# TSOC_RS485_EM.net
KiCad netlist of a schematic drawn in EAGLE
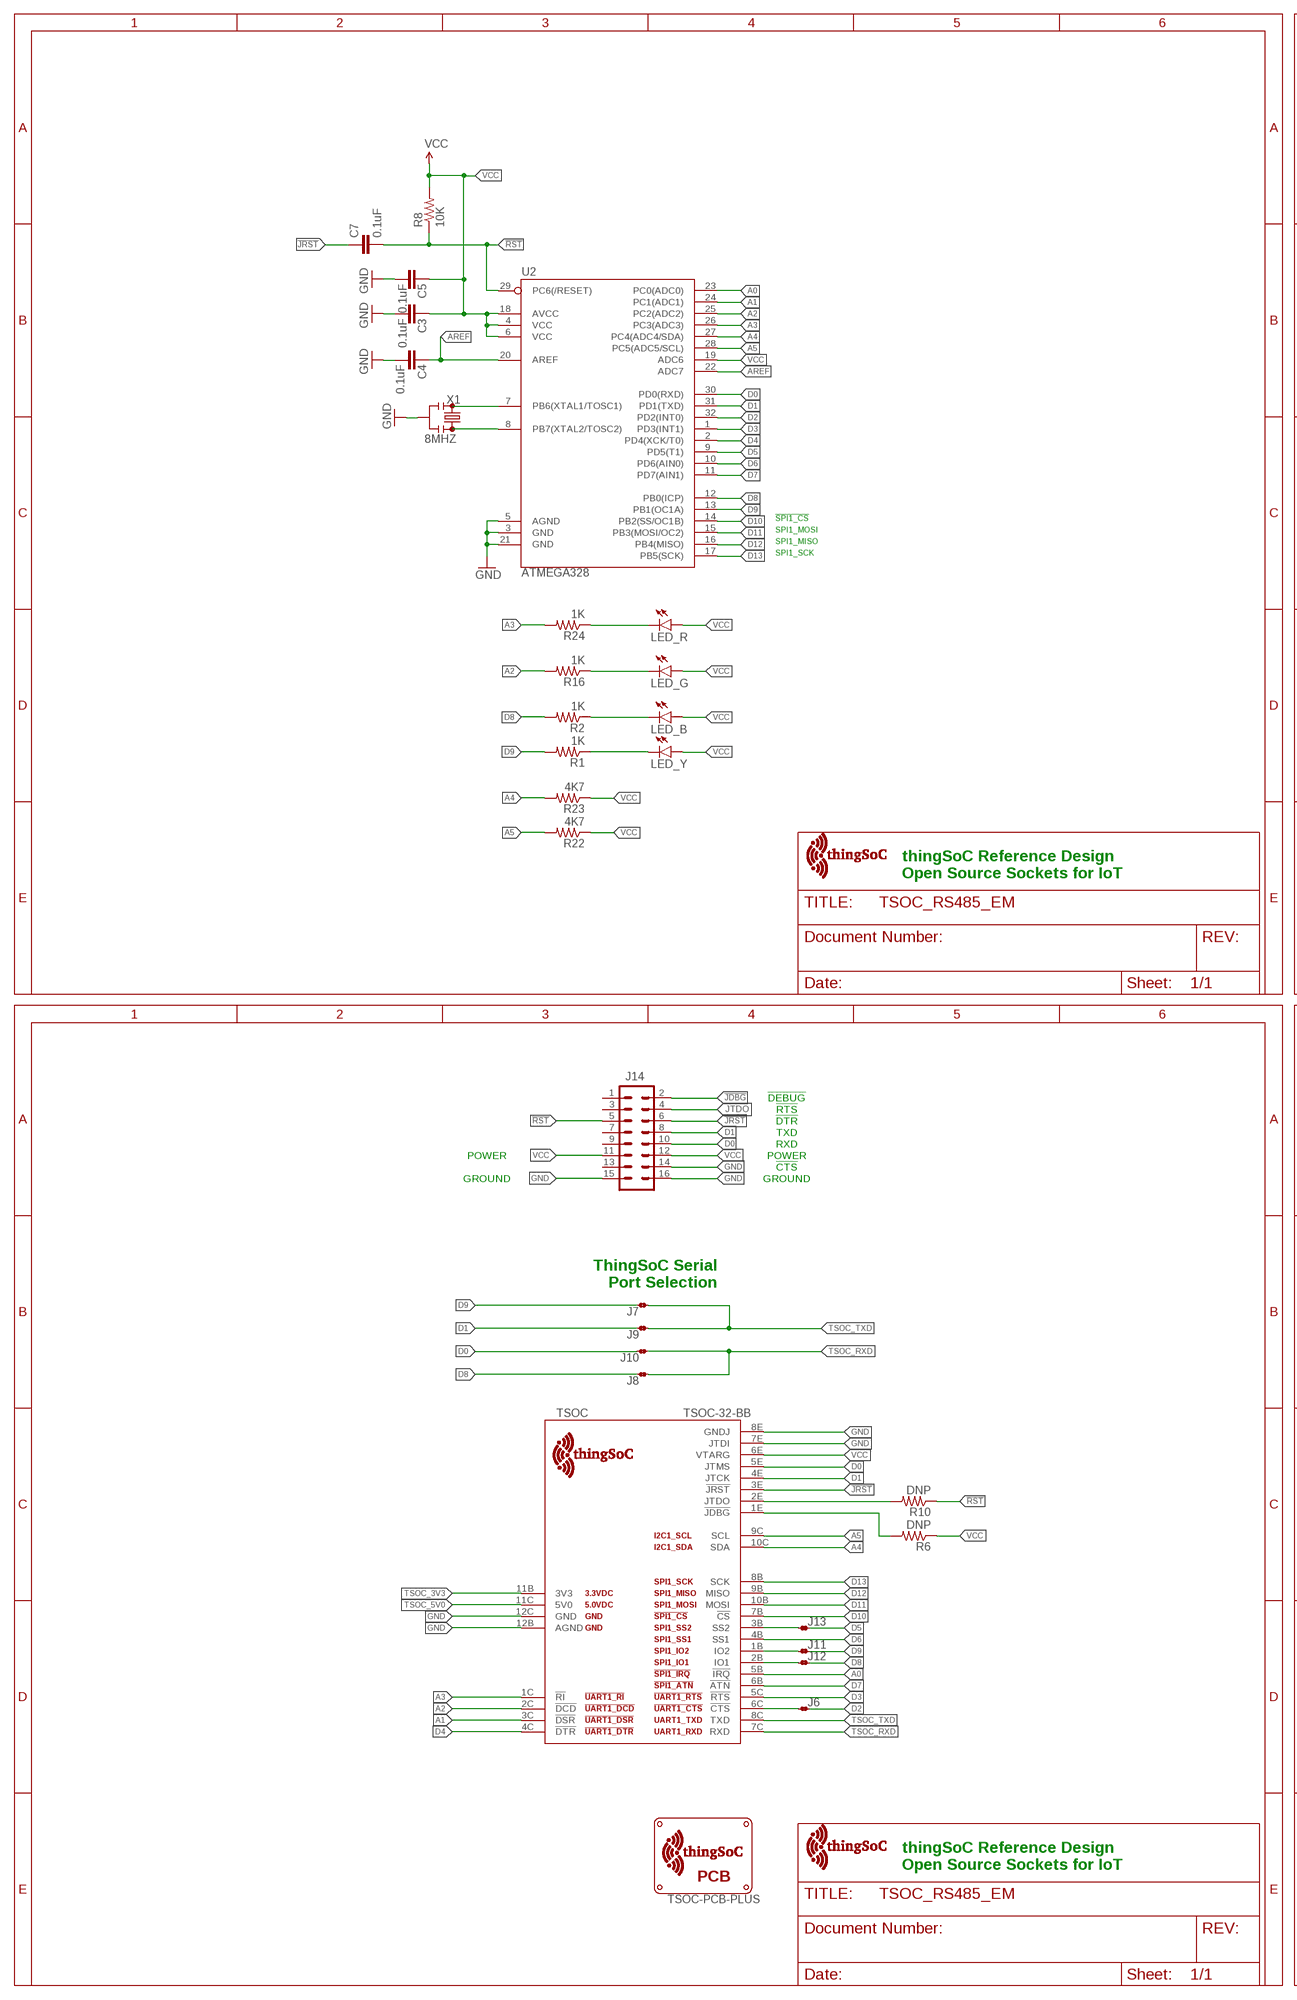
[diagram p0: schematic, sheet 1, part 1 of 2]
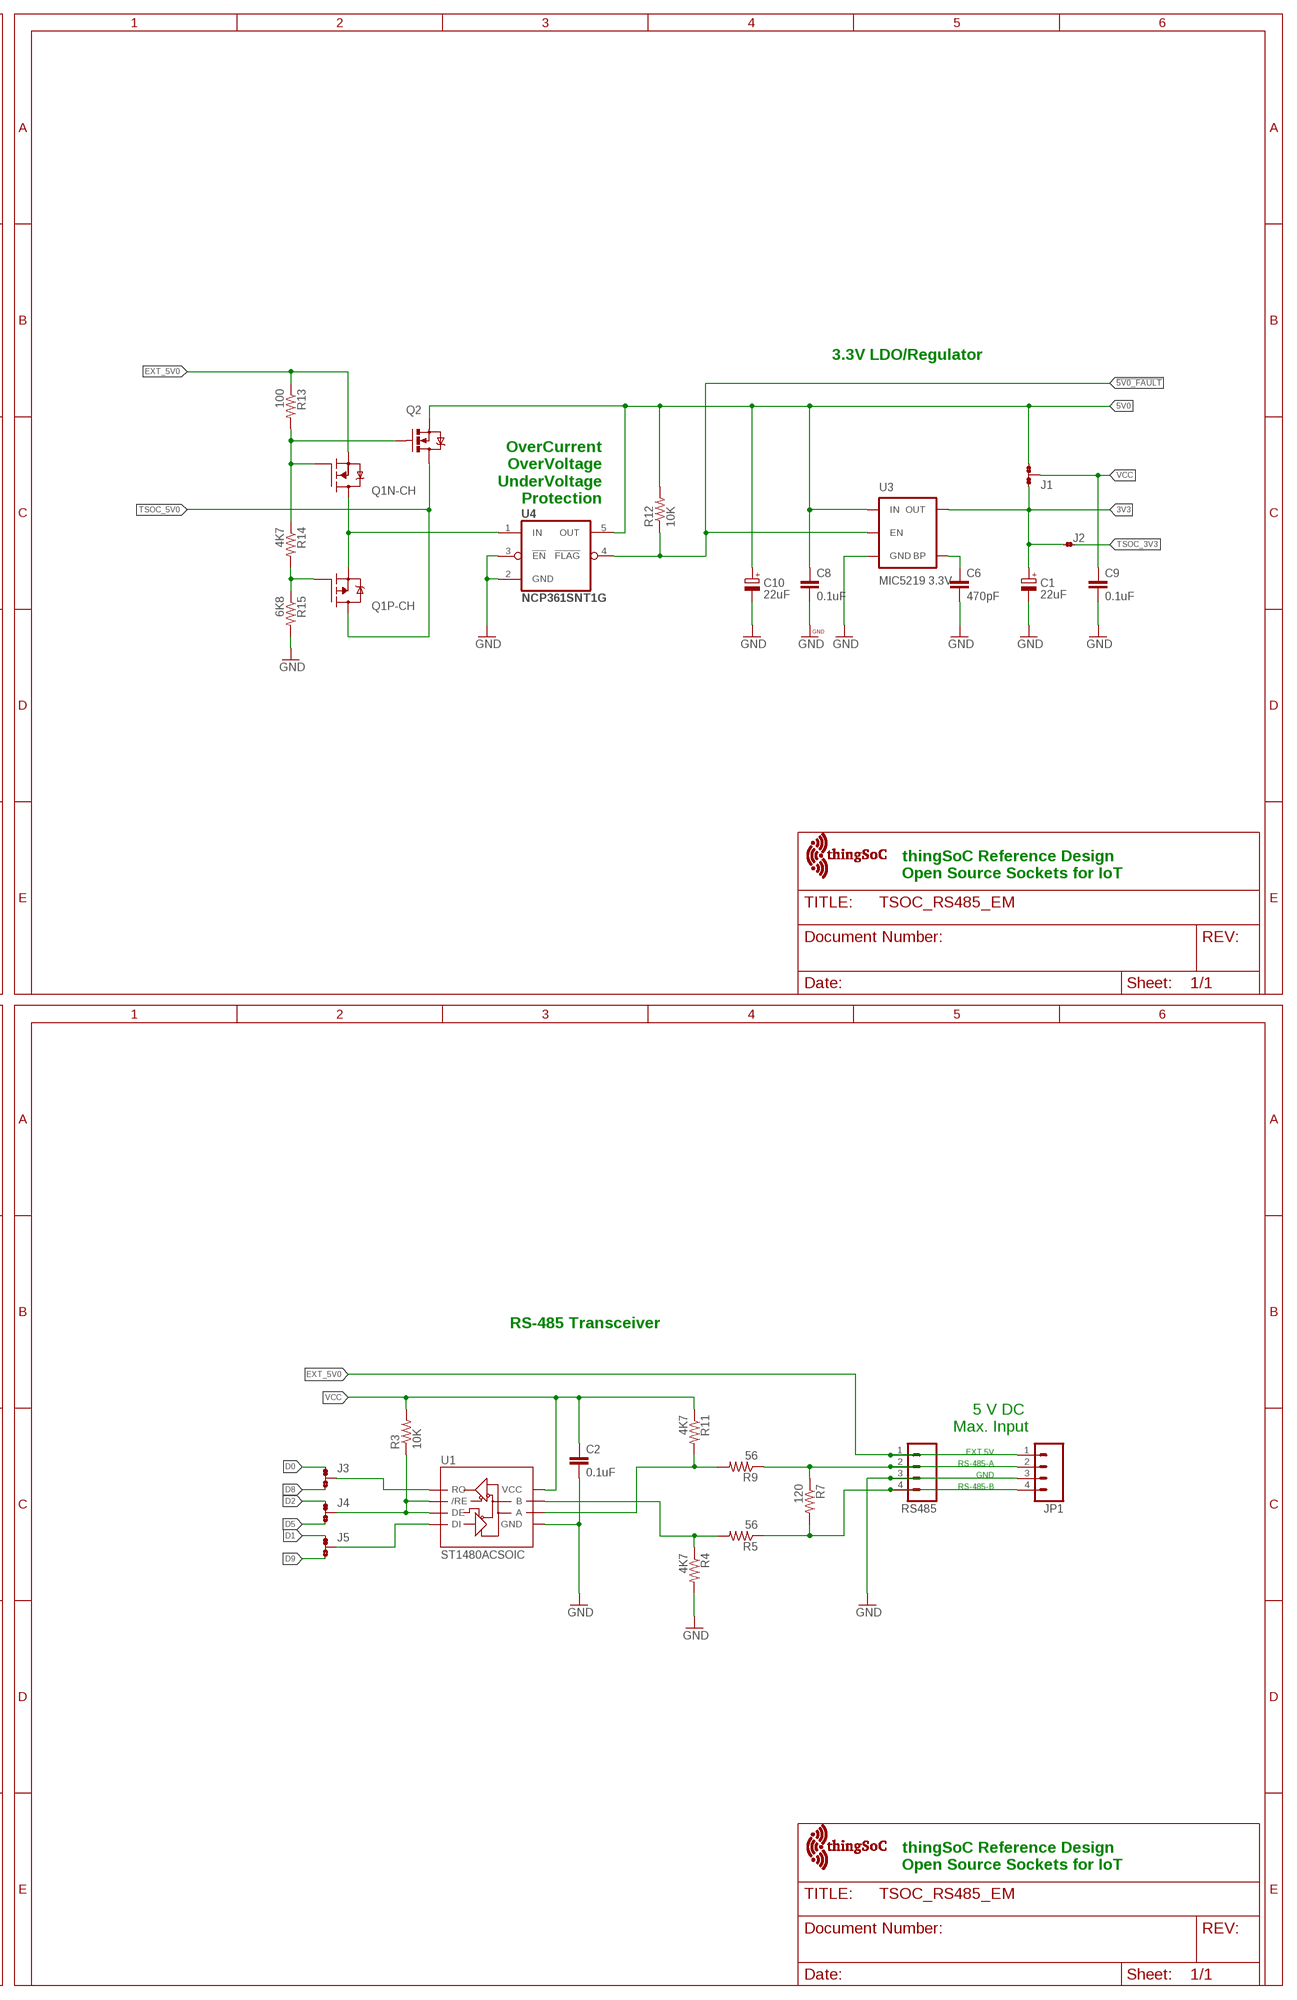
[diagram p1: schematic, sheet 1, part 2 of 2]

(export (version "E")
  (design (tool "Eeschema 10.0.6"))
  (components
    (comp (ref "C1")
      (value "22uF")
      (footprint "eagle-import:SMC_B")
      (libsource (lib "eagle-import") (part "CPOL-EUSMCB"))
    )
    (comp (ref "C2")
      (value "0.1uF")
      (footprint "eagle-import:EIA-0402")
      (libsource (lib "eagle-import") (part "CAPTYP"))
    )
    (comp (ref "C3")
      (value "0.1uF")
      (footprint "eagle-import:EIA-0402")
      (libsource (lib "eagle-import") (part "CAPTYP"))
    )
    (comp (ref "C4")
      (value "0.1uF")
      (footprint "eagle-import:EIA-0402")
      (libsource (lib "eagle-import") (part "CAPTYP"))
    )
    (comp (ref "C5")
      (value "0.1uF")
      (footprint "eagle-import:EIA-0402")
      (libsource (lib "eagle-import") (part "CAPTYP"))
    )
    (comp (ref "C6")
      (value "470pF")
      (footprint "eagle-import:EIA-0402")
      (libsource (lib "eagle-import") (part "CAPTYP"))
    )
    (comp (ref "C7")
      (value "0.1uF")
      (footprint "eagle-import:EIA-0402")
      (libsource (lib "eagle-import") (part "CAPTYP"))
    )
    (comp (ref "C8")
      (value "0.1uF")
      (footprint "eagle-import:EIA-0402")
      (libsource (lib "eagle-import") (part "CAPTYP"))
    )
    (comp (ref "C9")
      (value "0.1uF")
      (footprint "eagle-import:EIA-0402")
      (libsource (lib "eagle-import") (part "CAPTYP"))
    )
    (comp (ref "C10")
      (value "22uF")
      (footprint "eagle-import:SMC_B")
      (libsource (lib "eagle-import") (part "CPOL-EUSMCB"))
    )
    (comp (ref "J1")
      (value "JMP-3-1_2")
      (footprint "eagle-import:JMP-3-1_2")
      (libsource (lib "eagle-import") (part "JMP-3-1_2"))
    )
    (comp (ref "J2")
      (value "JMP-2-NC")
      (footprint "eagle-import:JMP-2-NC")
      (libsource (lib "eagle-import") (part "JMP-2-NC"))
    )
    (comp (ref "J3")
      (value "JMP-3-1_2")
      (footprint "eagle-import:JMP-3-1_2")
      (libsource (lib "eagle-import") (part "TSOC_RS485_EM_JMP-3-1_2"))
    )
    (comp (ref "J4")
      (value "JMP-3-1_2")
      (footprint "eagle-import:JMP-3-1_2")
      (libsource (lib "eagle-import") (part "TSOC_RS485_EM_JMP-3-1_2"))
    )
    (comp (ref "J5")
      (value "JMP-3-1_2")
      (footprint "eagle-import:JMP-3-1_2")
      (libsource (lib "eagle-import") (part "TSOC_RS485_EM_JMP-3-1_2"))
    )
    (comp (ref "J6")
      (value "JMP-2-NO")
      (footprint "eagle-import:JMP-2-NO")
      (libsource (lib "eagle-import") (part "JMP-2-NO"))
    )
    (comp (ref "J7")
      (value "JMP-2-NO")
      (footprint "eagle-import:JMP-2-NO")
      (libsource (lib "eagle-import") (part "JMP-2-NO"))
    )
    (comp (ref "J8")
      (value "JMP-2-NO")
      (footprint "eagle-import:JMP-2-NO")
      (libsource (lib "eagle-import") (part "JMP-2-NO"))
    )
    (comp (ref "J9")
      (value "JMP-2-NO")
      (footprint "eagle-import:JMP-2-NO")
      (libsource (lib "eagle-import") (part "JMP-2-NO"))
    )
    (comp (ref "J10")
      (value "JMP-2-NO")
      (footprint "eagle-import:JMP-2-NO")
      (libsource (lib "eagle-import") (part "JMP-2-NO"))
    )
    (comp (ref "J11")
      (value "JMP-2-NC")
      (footprint "eagle-import:JMP-2-NC")
      (libsource (lib "eagle-import") (part "JMP-2-NC"))
    )
    (comp (ref "J12")
      (value "JMP-2-NC")
      (footprint "eagle-import:JMP-2-NC")
      (libsource (lib "eagle-import") (part "JMP-2-NC"))
    )
    (comp (ref "J13")
      (value "JMP-2-NC")
      (footprint "eagle-import:JMP-2-NC")
      (libsource (lib "eagle-import") (part "JMP-2-NC"))
    )
    (comp (ref "J14")
      (value "M08X2")
      (footprint "eagle-import:2X8")
      (libsource (lib "eagle-import") (part "M08X2"))
    )
    (comp (ref "JP1")
      (value "M04PTH")
      (footprint "eagle-import:1X04")
      (libsource (lib "eagle-import") (part "M04PTH"))
    )
    (comp (ref "LED_B")
      (value "LED0603")
      (footprint "eagle-import:LED-0603")
      (libsource (lib "eagle-import") (part "LED0603"))
    )
    (comp (ref "LED_G")
      (value "LED0603")
      (footprint "eagle-import:LED-0603")
      (libsource (lib "eagle-import") (part "LED0603"))
    )
    (comp (ref "LED_R")
      (value "LED0603")
      (footprint "eagle-import:LED-0603")
      (libsource (lib "eagle-import") (part "LED0603"))
    )
    (comp (ref "LED_Y")
      (value "LED0603")
      (footprint "eagle-import:LED-0603")
      (libsource (lib "eagle-import") (part "LED0603"))
    )
    (comp (ref "Q1")
      (value "FDC6420C")
      (footprint "eagle-import:SOT95P280X110-6N")
      (libsource (lib "eagle-import") (part "FDC6420C"))
    )
    (comp (ref "Q2")
      (value "MOSFET-NCHANNELAO3404A")
      (footprint "eagle-import:SOT23-3")
      (libsource (lib "eagle-import") (part "MOSFET-NCHANNELAO3404A"))
    )
    (comp (ref "R1")
      (value "1K")
      (footprint "eagle-import:EIA-0402-MIN")
      (libsource (lib "eagle-import") (part "RESISTOR0402-MIN"))
    )
    (comp (ref "R2")
      (value "1K")
      (footprint "eagle-import:EIA-0402-MIN")
      (libsource (lib "eagle-import") (part "RESISTOR0402-MIN"))
    )
    (comp (ref "R3")
      (value "10K")
      (footprint "eagle-import:EIA-0402-MIN")
      (libsource (lib "eagle-import") (part "RESISTOR0402-MIN"))
    )
    (comp (ref "R4")
      (value "4K7")
      (footprint "eagle-import:EIA-0402-MIN")
      (libsource (lib "eagle-import") (part "RESISTOR0402-MIN"))
    )
    (comp (ref "R5")
      (value "56")
      (footprint "eagle-import:EIA-0402-MIN")
      (libsource (lib "eagle-import") (part "RESISTOR0402-MIN"))
    )
    (comp (ref "R6")
      (value "DNP")
      (footprint "eagle-import:EIA-0402-MIN")
      (libsource (lib "eagle-import") (part "RESISTOR0402-MIN"))
    )
    (comp (ref "R7")
      (value "120")
      (footprint "eagle-import:EIA-0402-MIN")
      (libsource (lib "eagle-import") (part "RESISTOR0402-MIN"))
    )
    (comp (ref "R8")
      (value "10K")
      (footprint "eagle-import:EIA-0402-MIN")
      (libsource (lib "eagle-import") (part "RESISTOR0402-MIN"))
    )
    (comp (ref "R9")
      (value "56")
      (footprint "eagle-import:EIA-0402-MIN")
      (libsource (lib "eagle-import") (part "RESISTOR0402-MIN"))
    )
    (comp (ref "R10")
      (value "DNP")
      (footprint "eagle-import:EIA-0402-MIN")
      (libsource (lib "eagle-import") (part "RESISTOR0402-MIN"))
    )
    (comp (ref "R11")
      (value "4K7")
      (footprint "eagle-import:EIA-0402-MIN")
      (libsource (lib "eagle-import") (part "RESISTOR0402-MIN"))
    )
    (comp (ref "R12")
      (value "10K")
      (footprint "eagle-import:EIA-0402-MIN")
      (libsource (lib "eagle-import") (part "RESISTOR0402-MIN"))
    )
    (comp (ref "R13")
      (value "100")
      (footprint "eagle-import:EIA-0402-MIN")
      (libsource (lib "eagle-import") (part "RESISTOR0402-MIN"))
    )
    (comp (ref "R14")
      (value "4K7")
      (footprint "eagle-import:EIA-0402-MIN")
      (libsource (lib "eagle-import") (part "RESISTOR0402-MIN"))
    )
    (comp (ref "R15")
      (value "6K8")
      (footprint "eagle-import:EIA-0402-MIN")
      (libsource (lib "eagle-import") (part "RESISTOR0402-MIN"))
    )
    (comp (ref "R16")
      (value "1K")
      (footprint "eagle-import:EIA-0402-MIN")
      (libsource (lib "eagle-import") (part "RESISTOR0402-MIN"))
    )
    (comp (ref "R22")
      (value "4K7")
      (footprint "eagle-import:EIA-0402-MIN")
      (libsource (lib "eagle-import") (part "RESISTOR0402-MIN"))
    )
    (comp (ref "R23")
      (value "4K7")
      (footprint "eagle-import:EIA-0402-MIN")
      (libsource (lib "eagle-import") (part "RESISTOR0402-MIN"))
    )
    (comp (ref "R24")
      (value "1K")
      (footprint "eagle-import:EIA-0402-MIN")
      (libsource (lib "eagle-import") (part "RESISTOR0402-MIN"))
    )
    (comp (ref "RS485")
      (value "M04SCREW")
      (footprint "eagle-import:SCREWTERMINAL-3.5MM-4")
      (libsource (lib "eagle-import") (part "M04SCREW"))
    )
    (comp (ref "TSOC")
      (value "TSOC-32-BB")
      (footprint "eagle-import:TSOC-BB-S32")
      (libsource (lib "eagle-import") (part "TSOC-32-BB"))
    )
    (comp (ref "U$3")
      (value "TSOC-PCB-PLUS")
      (footprint "eagle-import:TSOC-BB-BRD-PLUS")
      (libsource (lib "eagle-import") (part "TSOC-PCB-PLUS"))
    )
    (comp (ref "U$5")
      (value "TSOC-LOGO-SMALL")
      (footprint "eagle-import:TSOC-LOGO-SML")
      (libsource (lib "eagle-import") (part "TSOC-LOGO-SMALL"))
    )
    (comp (ref "U$6")
      (value "TSOC-LOGO-SMALL")
      (footprint "eagle-import:TSOC-LOGO-SML")
      (libsource (lib "eagle-import") (part "TSOC-LOGO-SMALL"))
    )
    (comp (ref "U$7")
      (value "TSOC-LOGO-SMALL")
      (footprint "eagle-import:TSOC-LOGO-SML")
      (libsource (lib "eagle-import") (part "TSOC-LOGO-SMALL"))
    )
    (comp (ref "U$8")
      (value "TSOC-LOGO-SMALL")
      (footprint "eagle-import:TSOC-LOGO-SML")
      (libsource (lib "eagle-import") (part "TSOC-LOGO-SMALL"))
    )
    (comp (ref "U1")
      (value "ST1480ACSOIC")
      (footprint "eagle-import:SO08")
      (libsource (lib "eagle-import") (part "ST1480ACSOIC"))
    )
    (comp (ref "U2")
      (value "ATMEGA328")
      (footprint "eagle-import:TQFP32-08")
      (libsource (lib "eagle-import") (part "ATMEGA168"))
    )
    (comp (ref "U3")
      (value "MIC5219 3.3V")
      (footprint "eagle-import:SOT23-5")
      (libsource (lib "eagle-import") (part "V_REG_MIC52193.3V"))
    )
    (comp (ref "U4")
      (value "NCP361SNT1G")
      (footprint "eagle-import:SOP95P275X110-5N")
      (libsource (lib "eagle-import") (part "NCP361SNT1G"))
    )
    (comp (ref "X1")
      (value "8MHZ")
      (footprint "eagle-import:RESONATOR-SMD")
      (libsource (lib "eagle-import") (part "RESONATOR8MHZ"))
    )
  )
  (nets
    (net (code "1") (name "/~{5V0_FAULT}") (class "Default")
      (node (ref "R12") (pin "1") (pinfunction "1_1") (pintype "passive"))
      (node (ref "U3") (pin "3") (pinfunction "EN_3") (pintype "input"))
      (node (ref "U4") (pin "4") (pinfunction "~{FLAG}_4") (pintype "input"))
    )
    (net (code "2") (name "/~{JDBG}") (class "Default")
      (node (ref "J14") (pin "2") (pinfunction "2_2") (pintype "passive"))
      (node (ref "R6") (pin "2") (pinfunction "2_2") (pintype "passive"))
      (node (ref "TSOC") (pin "1E") (pinfunction "~{JDBG}_1E") (pintype "bidirectional"))
    )
    (net (code "3") (name "/~{JRST}") (class "Default")
      (node (ref "C7") (pin "1") (pinfunction "1_1") (pintype "passive"))
      (node (ref "J14") (pin "6") (pinfunction "6_6") (pintype "passive"))
      (node (ref "TSOC") (pin "3E") (pinfunction "~{JRST}_3E") (pintype "bidirectional"))
    )
    (net (code "4") (name "/~{RST}") (class "Default")
      (node (ref "C7") (pin "2") (pinfunction "2_2") (pintype "passive"))
      (node (ref "J14") (pin "5") (pinfunction "5_5") (pintype "passive"))
      (node (ref "R10") (pin "1") (pinfunction "1_1") (pintype "passive"))
      (node (ref "R8") (pin "1") (pinfunction "1_1") (pintype "passive"))
      (node (ref "U2") (pin "29") (pinfunction "PC6(/RESET)_29") (pintype "bidirectional"))
    )
    (net (code "5") (name "3V3") (class "Default")
      (node (ref "C1") (pin "+") (pinfunction "+_+") (pintype "passive"))
      (node (ref "J1") (pin "1") (pinfunction "1_1") (pintype "passive"))
      (node (ref "J2") (pin "1") (pinfunction "1_1") (pintype "passive"))
      (node (ref "U3") (pin "5") (pinfunction "OUT_5") (pintype "passive"))
    )
    (net (code "6") (name "5V0") (class "Default")
      (node (ref "C10") (pin "+") (pinfunction "+_+") (pintype "passive"))
      (node (ref "C8") (pin "1") (pinfunction "1_1") (pintype "passive"))
      (node (ref "J1") (pin "3") (pinfunction "3_3") (pintype "passive"))
      (node (ref "Q2") (pin "2") (pinfunction "S_2") (pintype "passive"))
      (node (ref "R12") (pin "2") (pinfunction "2_2") (pintype "passive"))
      (node (ref "U3") (pin "1") (pinfunction "IN_1") (pintype "input"))
      (node (ref "U4") (pin "5") (pinfunction "OUT_5") (pintype "output"))
    )
    (net (code "7") (name "A0") (class "Default")
      (node (ref "TSOC") (pin "5B") (pinfunction "~{IRQ}_5B") (pintype "bidirectional"))
      (node (ref "U2") (pin "23") (pinfunction "PC0(ADC0)_23") (pintype "bidirectional"))
    )
    (net (code "8") (name "A1") (class "Default")
      (node (ref "TSOC") (pin "3C") (pinfunction "~{DSR}_3C") (pintype "bidirectional"))
      (node (ref "U2") (pin "24") (pinfunction "PC1(ADC1)_24") (pintype "bidirectional"))
    )
    (net (code "9") (name "A2") (class "Default")
      (node (ref "R16") (pin "2") (pinfunction "2_2") (pintype "passive"))
      (node (ref "TSOC") (pin "2C") (pinfunction "~{DCD}_2C") (pintype "bidirectional"))
      (node (ref "U2") (pin "25") (pinfunction "PC2(ADC2)_25") (pintype "bidirectional"))
    )
    (net (code "10") (name "A3") (class "Default")
      (node (ref "R24") (pin "2") (pinfunction "2_2") (pintype "passive"))
      (node (ref "TSOC") (pin "1C") (pinfunction "~{RI}_1C") (pintype "bidirectional"))
      (node (ref "U2") (pin "26") (pinfunction "PC3(ADC3)_26") (pintype "bidirectional"))
    )
    (net (code "11") (name "A4") (class "Default")
      (node (ref "R23") (pin "2") (pinfunction "2_2") (pintype "passive"))
      (node (ref "TSOC") (pin "10C") (pinfunction "SDA_10C") (pintype "bidirectional"))
      (node (ref "U2") (pin "27") (pinfunction "PC4(ADC4/SDA)_27") (pintype "bidirectional"))
    )
    (net (code "12") (name "A5") (class "Default")
      (node (ref "R22") (pin "2") (pinfunction "2_2") (pintype "passive"))
      (node (ref "TSOC") (pin "9C") (pinfunction "SCL_9C") (pintype "bidirectional"))
      (node (ref "U2") (pin "28") (pinfunction "PC5(ADC5/SCL)_28") (pintype "bidirectional"))
    )
    (net (code "13") (name "AREF") (class "Default")
      (node (ref "C4") (pin "2") (pinfunction "2_2") (pintype "passive"))
      (node (ref "U2") (pin "20") (pinfunction "AREF_20") (pintype "bidirectional"))
      (node (ref "U2") (pin "22") (pinfunction "ADC7_22") (pintype "bidirectional"))
    )
    (net (code "14") (name "D0") (class "Default")
      (node (ref "J10") (pin "2") (pinfunction "2_2") (pintype "passive"))
      (node (ref "J14") (pin "10") (pinfunction "10_10") (pintype "passive"))
      (node (ref "J3") (pin "1") (pinfunction "1_1") (pintype "passive"))
      (node (ref "TSOC") (pin "5E") (pinfunction "JTMS_5E") (pintype "bidirectional"))
      (node (ref "U2") (pin "30") (pinfunction "PD0(RXD)_30") (pintype "bidirectional"))
    )
    (net (code "15") (name "D1") (class "Default")
      (node (ref "J14") (pin "8") (pinfunction "8_8") (pintype "passive"))
      (node (ref "J5") (pin "1") (pinfunction "1_1") (pintype "passive"))
      (node (ref "J9") (pin "2") (pinfunction "2_2") (pintype "passive"))
      (node (ref "TSOC") (pin "4E") (pinfunction "JTCK_4E") (pintype "bidirectional"))
      (node (ref "U2") (pin "31") (pinfunction "PD1(TXD)_31") (pintype "bidirectional"))
    )
    (net (code "16") (name "D2") (class "Default")
      (node (ref "J4") (pin "1") (pinfunction "1_1") (pintype "passive"))
      (node (ref "J6") (pin "2") (pinfunction "2_2") (pintype "passive"))
      (node (ref "U2") (pin "32") (pinfunction "PD2(INT0)_32") (pintype "bidirectional"))
    )
    (net (code "17") (name "D3") (class "Default")
      (node (ref "TSOC") (pin "5C") (pinfunction "~{RTS}_5C") (pintype "bidirectional"))
      (node (ref "U2") (pin "1") (pinfunction "PD3(INT1)_1") (pintype "bidirectional"))
    )
    (net (code "18") (name "D4") (class "Default")
      (node (ref "TSOC") (pin "4C") (pinfunction "~{DTR}_4C") (pintype "bidirectional"))
      (node (ref "U2") (pin "2") (pinfunction "PD4(XCK/T0)_2") (pintype "bidirectional"))
    )
    (net (code "19") (name "D5") (class "Default")
      (node (ref "J13") (pin "2") (pinfunction "2_2") (pintype "passive"))
      (node (ref "J4") (pin "3") (pinfunction "3_3") (pintype "passive"))
      (node (ref "U2") (pin "9") (pinfunction "PD5(T1)_9") (pintype "bidirectional"))
    )
    (net (code "20") (name "D6") (class "Default")
      (node (ref "TSOC") (pin "4B") (pinfunction "SS1_4B") (pintype "bidirectional"))
      (node (ref "U2") (pin "10") (pinfunction "PD6(AIN0)_10") (pintype "bidirectional"))
    )
    (net (code "21") (name "D7") (class "Default")
      (node (ref "TSOC") (pin "6B") (pinfunction "~{ATN}_6B") (pintype "bidirectional"))
      (node (ref "U2") (pin "11") (pinfunction "PD7(AIN1)_11") (pintype "bidirectional"))
    )
    (net (code "22") (name "D8") (class "Default")
      (node (ref "J12") (pin "2") (pinfunction "2_2") (pintype "passive"))
      (node (ref "J3") (pin "3") (pinfunction "3_3") (pintype "passive"))
      (node (ref "J8") (pin "2") (pinfunction "2_2") (pintype "passive"))
      (node (ref "R2") (pin "2") (pinfunction "2_2") (pintype "passive"))
      (node (ref "U2") (pin "12") (pinfunction "PB0(ICP)_12") (pintype "bidirectional"))
    )
    (net (code "23") (name "D9") (class "Default")
      (node (ref "J11") (pin "2") (pinfunction "2_2") (pintype "passive"))
      (node (ref "J5") (pin "3") (pinfunction "3_3") (pintype "passive"))
      (node (ref "J7") (pin "2") (pinfunction "2_2") (pintype "passive"))
      (node (ref "R1") (pin "2") (pinfunction "2_2") (pintype "passive"))
      (node (ref "U2") (pin "13") (pinfunction "PB1(OC1A)_13") (pintype "bidirectional"))
    )
    (net (code "24") (name "D10") (class "Default")
      (node (ref "TSOC") (pin "7B") (pinfunction "~{CS}_7B") (pintype "bidirectional"))
      (node (ref "U2") (pin "14") (pinfunction "PB2(SS/OC1B)_14") (pintype "bidirectional"))
    )
    (net (code "25") (name "D11") (class "Default")
      (node (ref "TSOC") (pin "10B") (pinfunction "MOSI_10B") (pintype "bidirectional"))
      (node (ref "U2") (pin "15") (pinfunction "PB3(MOSI/OC2)_15") (pintype "bidirectional"))
    )
    (net (code "26") (name "D12") (class "Default")
      (node (ref "TSOC") (pin "9B") (pinfunction "MISO_9B") (pintype "bidirectional"))
      (node (ref "U2") (pin "16") (pinfunction "PB4(MISO)_16") (pintype "bidirectional"))
    )
    (net (code "27") (name "D13") (class "Default")
      (node (ref "TSOC") (pin "8B") (pinfunction "SCK_8B") (pintype "bidirectional"))
      (node (ref "U2") (pin "17") (pinfunction "PB5(SCK)_17") (pintype "bidirectional"))
    )
    (net (code "28") (name "EXT_5V0") (class "Default")
      (node (ref "JP1") (pin "1") (pinfunction "1_1") (pintype "passive"))
      (node (ref "Q1") (pin "5") (pinfunction "S_5") (pintype "passive"))
      (node (ref "R13") (pin "1") (pinfunction "1_1") (pintype "passive"))
      (node (ref "RS485") (pin "1") (pinfunction "1_1") (pintype "passive"))
    )
    (net (code "29") (name "GND") (class "Default")
      (node (ref "C1") (pin "-") (pinfunction "-_-") (pintype "passive"))
      (node (ref "C10") (pin "-") (pinfunction "-_-") (pintype "passive"))
      (node (ref "C2") (pin "2") (pinfunction "2_2") (pintype "passive"))
      (node (ref "C3") (pin "1") (pinfunction "1_1") (pintype "passive"))
      (node (ref "C4") (pin "1") (pinfunction "1_1") (pintype "passive"))
      (node (ref "C5") (pin "1") (pinfunction "1_1") (pintype "passive"))
      (node (ref "C6") (pin "2") (pinfunction "2_2") (pintype "passive"))
      (node (ref "C8") (pin "2") (pinfunction "2_2") (pintype "passive"))
      (node (ref "C9") (pin "2") (pinfunction "2_2") (pintype "passive"))
      (node (ref "J14") (pin "14") (pinfunction "14_14") (pintype "passive"))
      (node (ref "J14") (pin "15") (pinfunction "15_15") (pintype "passive"))
      (node (ref "J14") (pin "16") (pinfunction "16_16") (pintype "passive"))
      (node (ref "JP1") (pin "3") (pinfunction "3_3") (pintype "passive"))
      (node (ref "R15") (pin "2") (pinfunction "2_2") (pintype "passive"))
      (node (ref "R4") (pin "2") (pinfunction "2_2") (pintype "passive"))
      (node (ref "RS485") (pin "3") (pinfunction "3_3") (pintype "passive"))
      (node (ref "TSOC") (pin "12B") (pinfunction "AGND_12B") (pintype "bidirectional"))
      (node (ref "TSOC") (pin "12C") (pinfunction "GND_12C") (pintype "bidirectional"))
      (node (ref "TSOC") (pin "7E") (pinfunction "JTDI_7E") (pintype "bidirectional"))
      (node (ref "TSOC") (pin "8E") (pinfunction "GNDJ_8E") (pintype "bidirectional"))
      (node (ref "U1") (pin "5") (pinfunction "GND_5") (pintype "bidirectional"))
      (node (ref "U2") (pin "21") (pinfunction "GND_21") (pintype "bidirectional"))
      (node (ref "U2") (pin "3") (pinfunction "GND_3") (pintype "bidirectional"))
      (node (ref "U2") (pin "5") (pinfunction "AGND_5") (pintype "bidirectional"))
      (node (ref "U3") (pin "2") (pinfunction "GND_2") (pintype "input"))
      (node (ref "U4") (pin "2") (pinfunction "GND_2") (pintype "passive"))
      (node (ref "U4") (pin "3") (pinfunction "~{EN}_3") (pintype "input"))
      (node (ref "X1") (pin "2") (pinfunction "2_2") (pintype "passive"))
    )
    (net (code "30") (name "JTDO") (class "Default")
      (node (ref "J14") (pin "4") (pinfunction "4_4") (pintype "passive"))
      (node (ref "R10") (pin "2") (pinfunction "2_2") (pintype "passive"))
      (node (ref "TSOC") (pin "2E") (pinfunction "JTDO_2E") (pintype "bidirectional"))
    )
    (net (code "31") (name "Net-(JP1-Pad2)") (class "Default")
      (node (ref "JP1") (pin "2") (pinfunction "2_2") (pintype "passive"))
      (node (ref "R7") (pin "1") (pinfunction "1_1") (pintype "passive"))
      (node (ref "R9") (pin "1") (pinfunction "1_1") (pintype "passive"))
      (node (ref "RS485") (pin "2") (pinfunction "2_2") (pintype "passive"))
    )
    (net (code "32") (name "Net-(JP1-Pad4)") (class "Default")
      (node (ref "JP1") (pin "4") (pinfunction "4_4") (pintype "passive"))
      (node (ref "R5") (pin "1") (pinfunction "1_1") (pintype "passive"))
      (node (ref "R7") (pin "2") (pinfunction "2_2") (pintype "passive"))
      (node (ref "RS485") (pin "4") (pinfunction "4_4") (pintype "passive"))
    )
    (net (code "33") (name "Net-(LED_B-PadC)") (class "Default")
      (node (ref "LED_B") (pin "C") (pinfunction "C_C") (pintype "passive"))
      (node (ref "R2") (pin "1") (pinfunction "1_1") (pintype "passive"))
    )
    (net (code "34") (name "Net-(LED_G-PadC)") (class "Default")
      (node (ref "LED_G") (pin "C") (pinfunction "C_C") (pintype "passive"))
      (node (ref "R16") (pin "1") (pinfunction "1_1") (pintype "passive"))
    )
    (net (code "35") (name "Net-(LED_R-PadC)") (class "Default")
      (node (ref "LED_R") (pin "C") (pinfunction "C_C") (pintype "passive"))
      (node (ref "R24") (pin "1") (pinfunction "1_1") (pintype "passive"))
    )
    (net (code "36") (name "Net-(LED_Y-PadC)") (class "Default")
      (node (ref "LED_Y") (pin "C") (pinfunction "C_C") (pintype "passive"))
      (node (ref "R1") (pin "1") (pinfunction "1_1") (pintype "passive"))
    )
    (net (code "37") (name "Net-(Q1A-D)") (class "Default")
      (node (ref "Q1") (pin "2") (pinfunction "S_2") (pintype "passive"))
      (node (ref "Q1") (pin "6") (pinfunction "D_6") (pintype "passive"))
      (node (ref "U4") (pin "1") (pinfunction "IN_1") (pintype "power_in"))
    )
    (net (code "38") (name "Net-(Q1A-G)") (class "Default")
      (node (ref "Q1") (pin "1") (pinfunction "G_1") (pintype "passive"))
      (node (ref "Q2") (pin "1") (pinfunction "G_1") (pintype "passive"))
      (node (ref "R13") (pin "2") (pinfunction "2_2") (pintype "passive"))
      (node (ref "R14") (pin "1") (pinfunction "1_1") (pintype "passive"))
    )
    (net (code "39") (name "Net-(Q1B-G)") (class "Default")
      (node (ref "Q1") (pin "3") (pinfunction "G_3") (pintype "passive"))
      (node (ref "R14") (pin "2") (pinfunction "2_2") (pintype "passive"))
      (node (ref "R15") (pin "1") (pinfunction "1_1") (pintype "passive"))
    )
    (net (code "40") (name "Net-(TSOC-IO1)") (class "Default")
      (node (ref "J12") (pin "1") (pinfunction "1_1") (pintype "passive"))
      (node (ref "TSOC") (pin "2B") (pinfunction "IO1_2B") (pintype "bidirectional"))
    )
    (net (code "41") (name "Net-(TSOC-IO2)") (class "Default")
      (node (ref "J11") (pin "1") (pinfunction "1_1") (pintype "passive"))
      (node (ref "TSOC") (pin "1B") (pinfunction "IO2_1B") (pintype "bidirectional"))
    )
    (net (code "42") (name "Net-(TSOC-SS2)") (class "Default")
      (node (ref "J13") (pin "1") (pinfunction "1_1") (pintype "passive"))
      (node (ref "TSOC") (pin "3B") (pinfunction "SS2_3B") (pintype "bidirectional"))
    )
    (net (code "43") (name "Net-(TSOC-~{CTS})") (class "Default")
      (node (ref "J6") (pin "1") (pinfunction "1_1") (pintype "passive"))
      (node (ref "TSOC") (pin "6C") (pinfunction "~{CTS}_6C") (pintype "bidirectional"))
    )
    (net (code "44") (name "Net-(U1-A)") (class "Default")
      (node (ref "R11") (pin "2") (pinfunction "2_2") (pintype "passive"))
      (node (ref "R9") (pin "2") (pinfunction "2_2") (pintype "passive"))
      (node (ref "U1") (pin "6") (pinfunction "A_6") (pintype "bidirectional"))
    )
    (net (code "45") (name "Net-(U1-B)") (class "Default")
      (node (ref "R4") (pin "1") (pinfunction "1_1") (pintype "passive"))
      (node (ref "R5") (pin "2") (pinfunction "2_2") (pintype "passive"))
      (node (ref "U1") (pin "7") (pinfunction "B_7") (pintype "bidirectional"))
    )
    (net (code "46") (name "Net-(U1-DE)") (class "Default")
      (node (ref "J4") (pin "2") (pinfunction "2_2") (pintype "passive"))
      (node (ref "R3") (pin "1") (pinfunction "1_1") (pintype "passive"))
      (node (ref "U1") (pin "2") (pinfunction "/RE_2") (pintype "bidirectional"))
      (node (ref "U1") (pin "3") (pinfunction "DE_3") (pintype "bidirectional"))
    )
    (net (code "47") (name "Net-(U1-DI)") (class "Default")
      (node (ref "J5") (pin "2") (pinfunction "2_2") (pintype "passive"))
      (node (ref "U1") (pin "4") (pinfunction "DI_4") (pintype "bidirectional"))
    )
    (net (code "48") (name "Net-(U1-RO)") (class "Default")
      (node (ref "J3") (pin "2") (pinfunction "2_2") (pintype "passive"))
      (node (ref "U1") (pin "1") (pinfunction "RO_1") (pintype "bidirectional"))
    )
    (net (code "49") (name "Net-(U2-PB6(XTAL1{slash}TOSC1))") (class "Default")
      (node (ref "U2") (pin "7") (pinfunction "PB6(XTAL1/TOSC1)_7") (pintype "bidirectional"))
      (node (ref "X1") (pin "3") (pinfunction "3_3") (pintype "passive"))
    )
    (net (code "50") (name "Net-(U2-PB7(XTAL2{slash}TOSC2))") (class "Default")
      (node (ref "U2") (pin "8") (pinfunction "PB7(XTAL2/TOSC2)_8") (pintype "bidirectional"))
      (node (ref "X1") (pin "1") (pinfunction "1_1") (pintype "passive"))
    )
    (net (code "51") (name "Net-(U3-BP)") (class "Default")
      (node (ref "C6") (pin "1") (pinfunction "1_1") (pintype "passive"))
      (node (ref "U3") (pin "4") (pinfunction "BP_4") (pintype "input"))
    )
    (net (code "52") (name "TSOC_3V3") (class "Default")
      (node (ref "J2") (pin "2") (pinfunction "2_2") (pintype "passive"))
      (node (ref "TSOC") (pin "11B") (pinfunction "3V3_11B") (pintype "bidirectional"))
    )
    (net (code "53") (name "TSOC_5V0") (class "Default")
      (node (ref "Q1") (pin "4") (pinfunction "D_4") (pintype "passive"))
      (node (ref "Q2") (pin "3") (pinfunction "D_3") (pintype "passive"))
      (node (ref "TSOC") (pin "11C") (pinfunction "5V0_11C") (pintype "bidirectional"))
    )
    (net (code "54") (name "TSOC_RXD") (class "Default")
      (node (ref "J10") (pin "1") (pinfunction "1_1") (pintype "passive"))
      (node (ref "J8") (pin "1") (pinfunction "1_1") (pintype "passive"))
      (node (ref "TSOC") (pin "7C") (pinfunction "RXD_7C") (pintype "bidirectional"))
    )
    (net (code "55") (name "TSOC_TXD") (class "Default")
      (node (ref "J7") (pin "1") (pinfunction "1_1") (pintype "passive"))
      (node (ref "J9") (pin "1") (pinfunction "1_1") (pintype "passive"))
      (node (ref "TSOC") (pin "8C") (pinfunction "TXD_8C") (pintype "bidirectional"))
    )
    (net (code "56") (name "VCC") (class "Default")
      (node (ref "C2") (pin "1") (pinfunction "1_1") (pintype "passive"))
      (node (ref "C3") (pin "2") (pinfunction "2_2") (pintype "passive"))
      (node (ref "C5") (pin "2") (pinfunction "2_2") (pintype "passive"))
      (node (ref "C9") (pin "1") (pinfunction "1_1") (pintype "passive"))
      (node (ref "J1") (pin "2") (pinfunction "2_2") (pintype "passive"))
      (node (ref "J14") (pin "11") (pinfunction "11_11") (pintype "passive"))
      (node (ref "J14") (pin "12") (pinfunction "12_12") (pintype "passive"))
      (node (ref "LED_B") (pin "A") (pinfunction "A_A") (pintype "passive"))
      (node (ref "LED_G") (pin "A") (pinfunction "A_A") (pintype "passive"))
      (node (ref "LED_R") (pin "A") (pinfunction "A_A") (pintype "passive"))
      (node (ref "LED_Y") (pin "A") (pinfunction "A_A") (pintype "passive"))
      (node (ref "R11") (pin "1") (pinfunction "1_1") (pintype "passive"))
      (node (ref "R22") (pin "1") (pinfunction "1_1") (pintype "passive"))
      (node (ref "R23") (pin "1") (pinfunction "1_1") (pintype "passive"))
      (node (ref "R3") (pin "2") (pinfunction "2_2") (pintype "passive"))
      (node (ref "R6") (pin "1") (pinfunction "1_1") (pintype "passive"))
      (node (ref "R8") (pin "2") (pinfunction "2_2") (pintype "passive"))
      (node (ref "TSOC") (pin "6E") (pinfunction "VTARG_6E") (pintype "bidirectional"))
      (node (ref "U1") (pin "8") (pinfunction "VCC_8") (pintype "bidirectional"))
      (node (ref "U2") (pin "18") (pinfunction "AVCC_18") (pintype "bidirectional"))
      (node (ref "U2") (pin "19") (pinfunction "ADC6_19") (pintype "bidirectional"))
      (node (ref "U2") (pin "4") (pinfunction "VCC_4") (pintype "bidirectional"))
      (node (ref "U2") (pin "6") (pinfunction "VCC_6") (pintype "bidirectional"))
    )
    (net (code "57") (name "unconnected-(J14-Pad1)") (class "Default")
      (node (ref "J14") (pin "1") (pinfunction "1_1") (pintype "passive"))
    )
    (net (code "58") (name "unconnected-(J14-Pad3)") (class "Default")
      (node (ref "J14") (pin "3") (pinfunction "3_3") (pintype "passive"))
    )
    (net (code "59") (name "unconnected-(J14-Pad7)") (class "Default")
      (node (ref "J14") (pin "7") (pinfunction "7_7") (pintype "passive"))
    )
    (net (code "60") (name "unconnected-(J14-Pad9)") (class "Default")
      (node (ref "J14") (pin "9") (pinfunction "9_9") (pintype "passive"))
    )
    (net (code "61") (name "unconnected-(J14-Pad13)") (class "Default")
      (node (ref "J14") (pin "13") (pinfunction "13_13") (pintype "passive"))
    )
  )
)
